# main.net
KiCad netlist of a schematic drawn in EAGLE
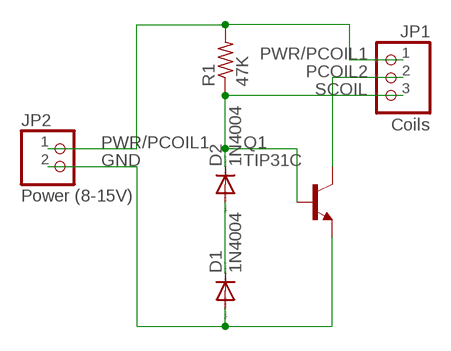
[diagram p0: schematic, sheet 1]

(export (version "E")
  (design (tool "Eeschema 10.0.6"))
  (components
    (comp (ref "D1")
      (value "1N4004")
      (footprint "eagle-import:DO41-10")
      (libsource (lib "eagle-import") (part "1N4004"))
    )
    (comp (ref "D2")
      (value "1N4004")
      (footprint "eagle-import:DO41-10")
      (libsource (lib "eagle-import") (part "1N4004"))
    )
    (comp (ref "JP1")
      (value "Coils")
      (footprint "eagle-import:1X03")
      (libsource (lib "eagle-import") (part "PINHD-1X3"))
    )
    (comp (ref "JP2")
      (value "Power (8-15V)")
      (footprint "eagle-import:1X02")
      (fields (field (name "SPICEPREFIX") "B"))
      (libsource (lib "eagle-import") (part "PINHD-1X2"))
    )
    (comp (ref "Q1")
      (value "TIP31C")
      (footprint "eagle-import:TO220")
      (libsource (lib "eagle-import") (part "TIP31C"))
    )
    (comp (ref "R1")
      (value "47K")
      (footprint "eagle-import:R2512")
      (libsource (lib "eagle-import") (part "R-US_R2512"))
    )
  )
  (nets
    (net (code "1") (name "/GND") (class "Default")
      (node (ref "D1") (pin "A") (pinfunction "A_A") (pintype "passive"))
      (node (ref "JP2") (pin "2") (pinfunction "2_2") (pintype "passive"))
      (node (ref "Q1") (pin "3") (pinfunction "E_3") (pintype "passive"))
    )
    (net (code "2") (name "/PCOIL2") (class "Default")
      (node (ref "JP1") (pin "2") (pinfunction "2_2") (pintype "passive"))
      (node (ref "Q1") (pin "2") (pinfunction "C_2") (pintype "passive"))
    )
    (net (code "3") (name "/PWR{slash}PCOIL1") (class "Default")
      (node (ref "JP1") (pin "1") (pinfunction "1_1") (pintype "passive"))
      (node (ref "JP2") (pin "1") (pinfunction "1_1") (pintype "passive"))
      (node (ref "R1") (pin "2") (pinfunction "2_2") (pintype "passive"))
    )
    (net (code "4") (name "/SCOIL") (class "Default")
      (node (ref "D2") (pin "C") (pinfunction "C_C") (pintype "passive"))
      (node (ref "JP1") (pin "3") (pinfunction "3_3") (pintype "passive"))
      (node (ref "Q1") (pin "1") (pinfunction "B_1") (pintype "passive"))
      (node (ref "R1") (pin "1") (pinfunction "1_1") (pintype "passive"))
    )
    (net (code "5") (name "Net-(D1-PadC)") (class "Default")
      (node (ref "D1") (pin "C") (pinfunction "C_C") (pintype "passive"))
      (node (ref "D2") (pin "A") (pinfunction "A_A") (pintype "passive"))
    )
  )
)
